# crunchboy.net
KiCad netlist of a schematic drawn in EAGLE
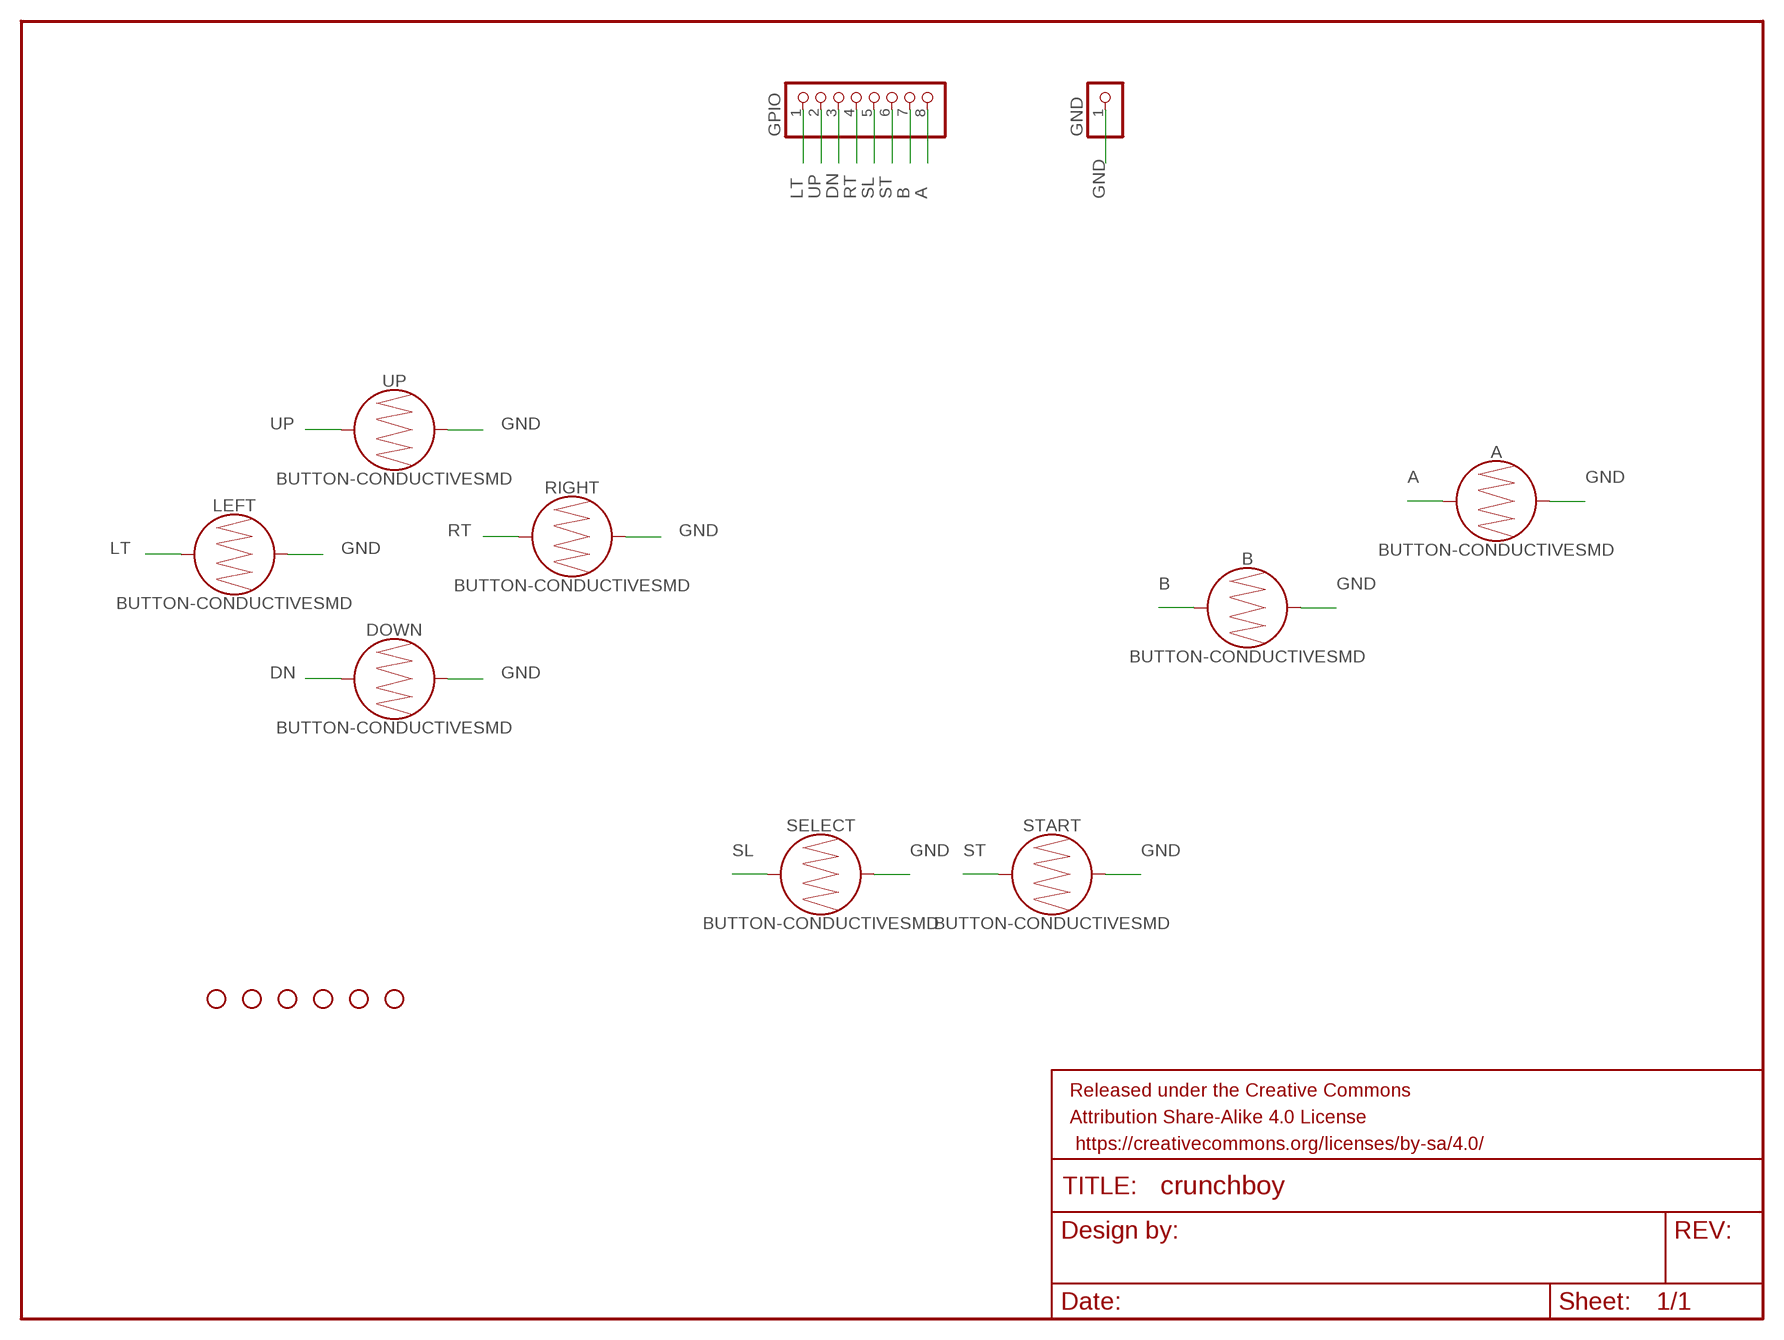
[diagram p0: schematic, sheet 1]

(export (version "E")
  (design (tool "Eeschema 10.0.6"))
  (components
    (comp (ref "A")
      (value "BUTTON-CONDUCTIVESMD")
      (footprint "eagle-import:BUTTON-CONDUCTIVE")
      (libsource (lib "eagle-import") (part "BUTTON-CONDUCTIVESMD"))
    )
    (comp (ref "B")
      (value "BUTTON-CONDUCTIVESMD")
      (footprint "eagle-import:BUTTON-CONDUCTIVE")
      (libsource (lib "eagle-import") (part "BUTTON-CONDUCTIVESMD"))
    )
    (comp (ref "DOWN")
      (value "BUTTON-CONDUCTIVESMD")
      (footprint "eagle-import:BUTTON-CONDUCTIVE")
      (libsource (lib "eagle-import") (part "BUTTON-CONDUCTIVESMD"))
    )
    (comp (ref "FRAME1")
      (value "FRAME-LETTER")
      (footprint "eagle-import:CREATIVE_COMMONS")
      (libsource (lib "eagle-import") (part "FRAME-LETTER"))
    )
    (comp (ref "GND")
      (value "PINHD-1X1")
      (footprint "eagle-import:1X01")
      (libsource (lib "eagle-import") (part "PINHD-1X1"))
    )
    (comp (ref "GPIO")
      (value "PINHD-1X8")
      (footprint "eagle-import:1X08")
      (libsource (lib "eagle-import") (part "PINHD-1X8"))
    )
    (comp (ref "H10")
      (value "STAND-OFF")
      (footprint "eagle-import:STAND-OFF")
      (libsource (lib "eagle-import") (part "STAND-OFF"))
    )
    (comp (ref "H11")
      (value "STAND-OFF")
      (footprint "eagle-import:STAND-OFF")
      (libsource (lib "eagle-import") (part "STAND-OFF"))
    )
    (comp (ref "H12")
      (value "STAND-OFF")
      (footprint "eagle-import:STAND-OFF")
      (libsource (lib "eagle-import") (part "STAND-OFF"))
    )
    (comp (ref "H13")
      (value "STAND-OFF")
      (footprint "eagle-import:STAND-OFF")
      (libsource (lib "eagle-import") (part "STAND-OFF"))
    )
    (comp (ref "H15")
      (value "STAND-OFF")
      (footprint "eagle-import:STAND-OFF")
      (libsource (lib "eagle-import") (part "STAND-OFF"))
    )
    (comp (ref "H16")
      (value "STAND-OFF")
      (footprint "eagle-import:STAND-OFF")
      (libsource (lib "eagle-import") (part "STAND-OFF"))
    )
    (comp (ref "LEFT")
      (value "BUTTON-CONDUCTIVESMD")
      (footprint "eagle-import:BUTTON-CONDUCTIVE")
      (libsource (lib "eagle-import") (part "BUTTON-CONDUCTIVESMD"))
    )
    (comp (ref "RIGHT")
      (value "BUTTON-CONDUCTIVESMD")
      (footprint "eagle-import:BUTTON-CONDUCTIVE")
      (libsource (lib "eagle-import") (part "BUTTON-CONDUCTIVESMD"))
    )
    (comp (ref "SELECT")
      (value "BUTTON-CONDUCTIVESMD")
      (footprint "eagle-import:BUTTON-CONDUCTIVE")
      (libsource (lib "eagle-import") (part "BUTTON-CONDUCTIVESMD"))
    )
    (comp (ref "START")
      (value "BUTTON-CONDUCTIVESMD")
      (footprint "eagle-import:BUTTON-CONDUCTIVE")
      (libsource (lib "eagle-import") (part "BUTTON-CONDUCTIVESMD"))
    )
    (comp (ref "UP")
      (value "BUTTON-CONDUCTIVESMD")
      (footprint "eagle-import:BUTTON-CONDUCTIVE")
      (libsource (lib "eagle-import") (part "BUTTON-CONDUCTIVESMD"))
    )
  )
  (nets
    (net (code "1") (name "/A") (class "Default")
      (node (ref "A") (pin "1") (pinfunction "1_1") (pintype "passive"))
      (node (ref "GPIO") (pin "8") (pinfunction "8_8") (pintype "passive"))
    )
    (net (code "2") (name "/B") (class "Default")
      (node (ref "B") (pin "1") (pinfunction "1_1") (pintype "passive"))
      (node (ref "GPIO") (pin "7") (pinfunction "7_7") (pintype "passive"))
    )
    (net (code "3") (name "/DN") (class "Default")
      (node (ref "DOWN") (pin "1") (pinfunction "1_1") (pintype "passive"))
      (node (ref "GPIO") (pin "3") (pinfunction "3_3") (pintype "passive"))
    )
    (net (code "4") (name "/GND") (class "Default")
      (node (ref "A") (pin "2") (pinfunction "2_2") (pintype "passive"))
      (node (ref "B") (pin "2") (pinfunction "2_2") (pintype "passive"))
      (node (ref "DOWN") (pin "2") (pinfunction "2_2") (pintype "passive"))
      (node (ref "GND") (pin "1") (pinfunction "1_1") (pintype "passive"))
      (node (ref "LEFT") (pin "2") (pinfunction "2_2") (pintype "passive"))
      (node (ref "RIGHT") (pin "2") (pinfunction "2_2") (pintype "passive"))
      (node (ref "SELECT") (pin "2") (pinfunction "2_2") (pintype "passive"))
      (node (ref "START") (pin "2") (pinfunction "2_2") (pintype "passive"))
      (node (ref "UP") (pin "2") (pinfunction "2_2") (pintype "passive"))
    )
    (net (code "5") (name "/LT") (class "Default")
      (node (ref "GPIO") (pin "1") (pinfunction "1_1") (pintype "passive"))
      (node (ref "LEFT") (pin "1") (pinfunction "1_1") (pintype "passive"))
    )
    (net (code "6") (name "/RT") (class "Default")
      (node (ref "GPIO") (pin "4") (pinfunction "4_4") (pintype "passive"))
      (node (ref "RIGHT") (pin "1") (pinfunction "1_1") (pintype "passive"))
    )
    (net (code "7") (name "/SL") (class "Default")
      (node (ref "GPIO") (pin "5") (pinfunction "5_5") (pintype "passive"))
      (node (ref "SELECT") (pin "1") (pinfunction "1_1") (pintype "passive"))
    )
    (net (code "8") (name "/ST") (class "Default")
      (node (ref "GPIO") (pin "6") (pinfunction "6_6") (pintype "passive"))
      (node (ref "START") (pin "1") (pinfunction "1_1") (pintype "passive"))
    )
    (net (code "9") (name "/UP") (class "Default")
      (node (ref "GPIO") (pin "2") (pinfunction "2_2") (pintype "passive"))
      (node (ref "UP") (pin "1") (pinfunction "1_1") (pintype "passive"))
    )
  )
)
